# JH_Debug.net
KiCad netlist of a schematic drawn in Altium Designer
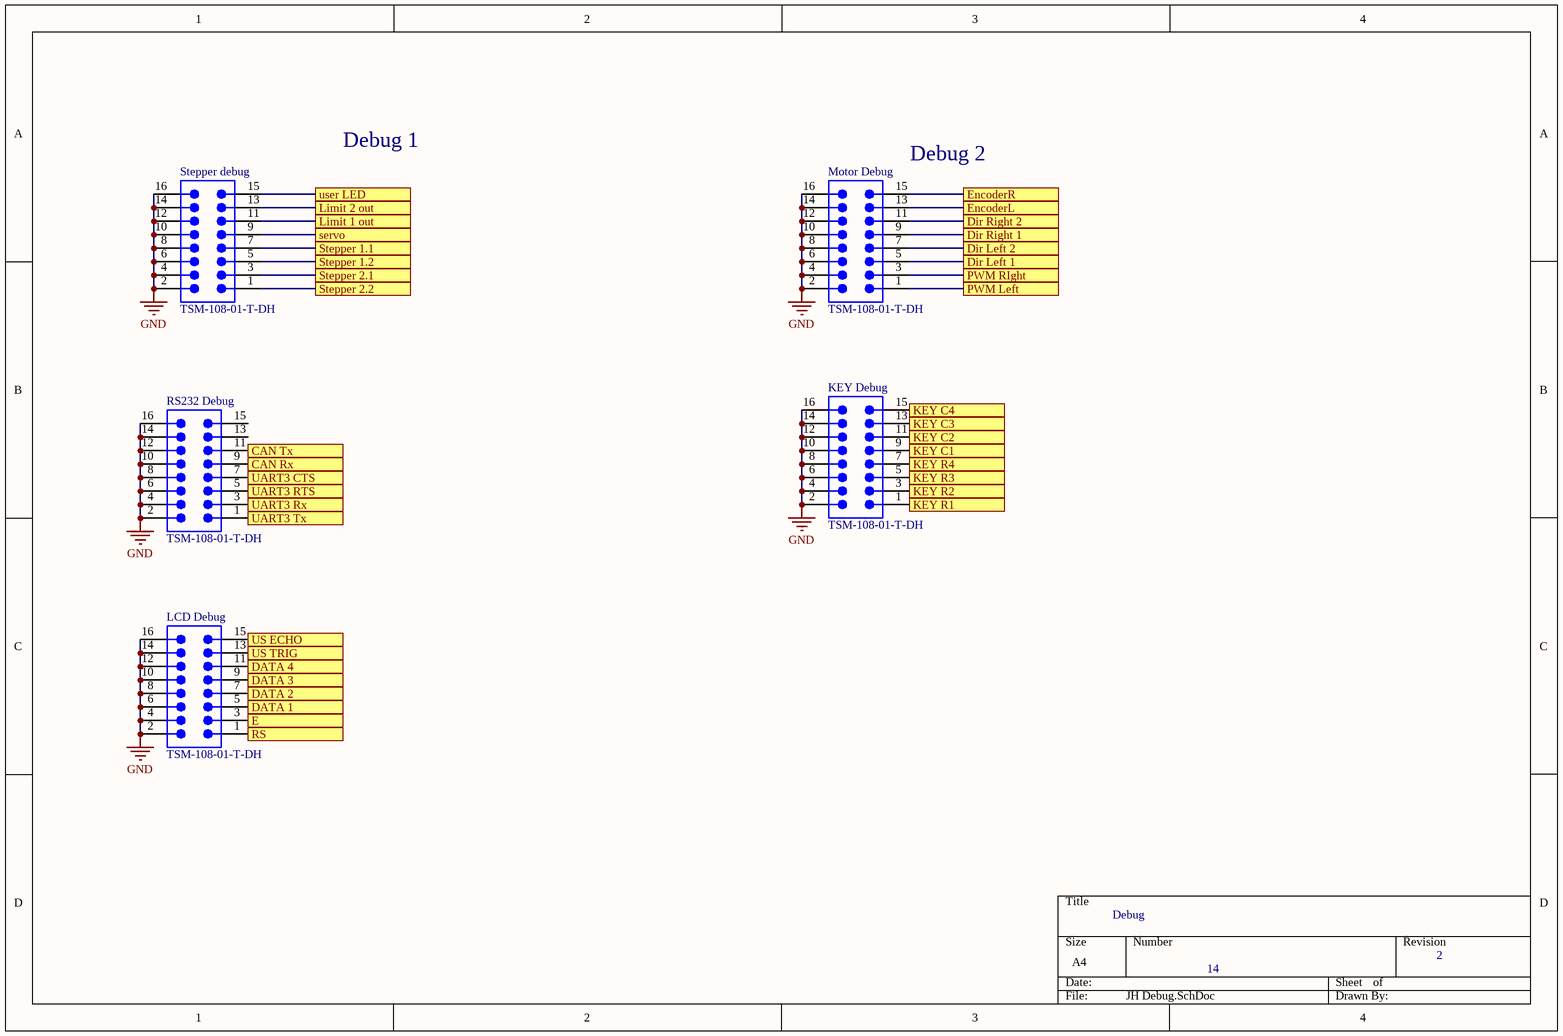
[diagram p0: JH Debug.SchDoc]

(export (version "E")
  (design (tool "Eeschema 10.0.6"))
  (components
    (comp (ref "KEY Debug")
      (value "TSM-108-01-T-DH")
      (footprint "SMTC-TSM-108-01-X-DH")
      (fields (field (name "MANUFACTURER") "Samtec"))
      (libsource (lib "Altium Content Vault") (part "SMTC-TSM-108-01-X-X"))
    )
    (comp (ref "LCD Debug")
      (value "TSM-108-01-T-DH")
      (footprint "SMTC-TSM-108-01-X-DH")
      (fields (field (name "MANUFACTURER") "Samtec"))
      (libsource (lib "Altium Content Vault") (part "SMTC-TSM-108-01-X-X"))
    )
    (comp (ref "Motor Debug")
      (value "TSM-108-01-T-DH")
      (footprint "SMTC-TSM-108-01-X-DH")
      (fields (field (name "MANUFACTURER") "Samtec"))
      (libsource (lib "Altium Content Vault") (part "SMTC-TSM-108-01-X-X"))
    )
    (comp (ref "RS232 Debug")
      (value "TSM-108-01-T-DH")
      (footprint "SMTC-TSM-108-01-X-DH")
      (fields (field (name "MANUFACTURER") "Samtec"))
      (libsource (lib "Altium Content Vault") (part "SMTC-TSM-108-01-X-X"))
    )
    (comp (ref "Stepper debug")
      (value "TSM-108-01-T-DH")
      (footprint "SMTC-TSM-108-01-X-DH")
      (fields (field (name "MANUFACTURER") "Samtec"))
      (libsource (lib "Altium Content Vault") (part "SMTC-TSM-108-01-X-X"))
    )
  )
  (nets
    (net (code "7") (name "/CAN Rx") (class "Default")
      (node (ref "RS232 Debug") (pin "9") (pinfunction "9_9") (pintype "passive"))
    )
    (net (code "8") (name "/CAN Tx") (class "Default")
      (node (ref "RS232 Debug") (pin "11") (pinfunction "11_11") (pintype "passive"))
    )
    (net (code "9") (name "/DATA 1") (class "Default")
      (node (ref "LCD Debug") (pin "5") (pinfunction "5_5") (pintype "passive"))
    )
    (net (code "10") (name "/DATA 2") (class "Default")
      (node (ref "LCD Debug") (pin "7") (pinfunction "7_7") (pintype "passive"))
    )
    (net (code "12") (name "/DATA 3") (class "Default")
      (node (ref "LCD Debug") (pin "9") (pinfunction "9_9") (pintype "passive"))
    )
    (net (code "13") (name "/DATA 4") (class "Default")
      (node (ref "LCD Debug") (pin "11") (pinfunction "11_11") (pintype "passive"))
    )
    (net (code "22") (name "/Dir Left 1") (class "Default")
      (node (ref "Motor Debug") (pin "5") (pinfunction "5_5") (pintype "passive"))
    )
    (net (code "23") (name "/Dir Left 2") (class "Default")
      (node (ref "Motor Debug") (pin "7") (pinfunction "7_7") (pintype "passive"))
    )
    (net (code "24") (name "/Dir Right 1") (class "Default")
      (node (ref "Motor Debug") (pin "9") (pinfunction "9_9") (pintype "passive"))
    )
    (net (code "25") (name "/Dir Right 2") (class "Default")
      (node (ref "Motor Debug") (pin "11") (pinfunction "11_11") (pintype "passive"))
    )
    (net (code "27") (name "/E") (class "Default")
      (node (ref "LCD Debug") (pin "3") (pinfunction "3_3") (pintype "passive"))
    )
    (net (code "28") (name "/EncoderL") (class "Default")
      (node (ref "Motor Debug") (pin "13") (pinfunction "13_13") (pintype "passive"))
    )
    (net (code "29") (name "/EncoderR") (class "Default")
      (node (ref "Motor Debug") (pin "15") (pinfunction "15_15") (pintype "passive"))
    )
    (net (code "30") (name "/KEY C1") (class "Default")
      (node (ref "KEY Debug") (pin "9") (pinfunction "9_9") (pintype "passive"))
    )
    (net (code "37") (name "/KEY C2") (class "Default")
      (node (ref "KEY Debug") (pin "11") (pinfunction "11_11") (pintype "passive"))
    )
    (net (code "38") (name "/KEY C3") (class "Default")
      (node (ref "KEY Debug") (pin "13") (pinfunction "13_13") (pintype "passive"))
    )
    (net (code "39") (name "/KEY C4") (class "Default")
      (node (ref "KEY Debug") (pin "15") (pinfunction "15_15") (pintype "passive"))
    )
    (net (code "40") (name "/KEY R1") (class "Default")
      (node (ref "KEY Debug") (pin "1") (pinfunction "1_1") (pintype "passive"))
    )
    (net (code "41") (name "/KEY R2") (class "Default")
      (node (ref "KEY Debug") (pin "3") (pinfunction "3_3") (pintype "passive"))
    )
    (net (code "42") (name "/KEY R3") (class "Default")
      (node (ref "KEY Debug") (pin "5") (pinfunction "5_5") (pintype "passive"))
    )
    (net (code "43") (name "/KEY R4") (class "Default")
      (node (ref "KEY Debug") (pin "7") (pinfunction "7_7") (pintype "passive"))
    )
    (net (code "44") (name "/Limit 1 out") (class "Default")
      (node (ref "Stepper debug") (pin "11") (pinfunction "11_11") (pintype "passive"))
    )
    (net (code "45") (name "/Limit 2 out") (class "Default")
      (node (ref "Stepper debug") (pin "13") (pinfunction "13_13") (pintype "passive"))
    )
    (net (code "46") (name "/PWM Left") (class "Default")
      (node (ref "Motor Debug") (pin "1") (pinfunction "1_1") (pintype "passive"))
    )
    (net (code "47") (name "/PWM RIght") (class "Default")
      (node (ref "Motor Debug") (pin "3") (pinfunction "3_3") (pintype "passive"))
    )
    (net (code "48") (name "/RS") (class "Default")
      (node (ref "LCD Debug") (pin "1") (pinfunction "1_1") (pintype "passive"))
    )
    (net (code "49") (name "/Stepper 1.1") (class "Default")
      (node (ref "Stepper debug") (pin "7") (pinfunction "7_7") (pintype "passive"))
    )
    (net (code "50") (name "/Stepper 1.2") (class "Default")
      (node (ref "Stepper debug") (pin "5") (pinfunction "5_5") (pintype "passive"))
    )
    (net (code "51") (name "/Stepper 2.1") (class "Default")
      (node (ref "Stepper debug") (pin "3") (pinfunction "3_3") (pintype "passive"))
    )
    (net (code "52") (name "/Stepper 2.2") (class "Default")
      (node (ref "Stepper debug") (pin "1") (pinfunction "1_1") (pintype "passive"))
    )
    (net (code "53") (name "/UART3 CTS") (class "Default")
      (node (ref "RS232 Debug") (pin "7") (pinfunction "7_7") (pintype "passive"))
    )
    (net (code "54") (name "/UART3 RTS") (class "Default")
      (node (ref "RS232 Debug") (pin "5") (pinfunction "5_5") (pintype "passive"))
    )
    (net (code "55") (name "/UART3 Rx") (class "Default")
      (node (ref "RS232 Debug") (pin "3") (pinfunction "3_3") (pintype "passive"))
    )
    (net (code "56") (name "/UART3 Tx") (class "Default")
      (node (ref "RS232 Debug") (pin "1") (pinfunction "1_1") (pintype "passive"))
    )
    (net (code "57") (name "/US ECHO") (class "Default")
      (node (ref "LCD Debug") (pin "15") (pinfunction "15_15") (pintype "passive"))
    )
    (net (code "58") (name "/US TRIG") (class "Default")
      (node (ref "LCD Debug") (pin "13") (pinfunction "13_13") (pintype "passive"))
    )
    (net (code "59") (name "/servo") (class "Default")
      (node (ref "Stepper debug") (pin "9") (pinfunction "9_9") (pintype "passive"))
    )
    (net (code "60") (name "/user LED") (class "Default")
      (node (ref "Stepper debug") (pin "15") (pinfunction "15_15") (pintype "passive"))
    )
    (net (code "61") (name "GND") (class "Default")
      (node (ref "KEY Debug") (pin "10") (pinfunction "10_10") (pintype "passive"))
      (node (ref "KEY Debug") (pin "12") (pinfunction "12_12") (pintype "passive"))
      (node (ref "KEY Debug") (pin "14") (pinfunction "14_14") (pintype "passive"))
      (node (ref "KEY Debug") (pin "16") (pinfunction "16_16") (pintype "passive"))
      (node (ref "KEY Debug") (pin "2") (pinfunction "2_2") (pintype "passive"))
      (node (ref "KEY Debug") (pin "4") (pinfunction "4_4") (pintype "passive"))
      (node (ref "KEY Debug") (pin "6") (pinfunction "6_6") (pintype "passive"))
      (node (ref "KEY Debug") (pin "8") (pinfunction "8_8") (pintype "passive"))
      (node (ref "LCD Debug") (pin "10") (pinfunction "10_10") (pintype "passive"))
      (node (ref "LCD Debug") (pin "12") (pinfunction "12_12") (pintype "passive"))
      (node (ref "LCD Debug") (pin "14") (pinfunction "14_14") (pintype "passive"))
      (node (ref "LCD Debug") (pin "16") (pinfunction "16_16") (pintype "passive"))
      (node (ref "LCD Debug") (pin "2") (pinfunction "2_2") (pintype "passive"))
      (node (ref "LCD Debug") (pin "4") (pinfunction "4_4") (pintype "passive"))
      (node (ref "LCD Debug") (pin "6") (pinfunction "6_6") (pintype "passive"))
      (node (ref "LCD Debug") (pin "8") (pinfunction "8_8") (pintype "passive"))
      (node (ref "Motor Debug") (pin "10") (pinfunction "10_10") (pintype "passive"))
      (node (ref "Motor Debug") (pin "12") (pinfunction "12_12") (pintype "passive"))
      (node (ref "Motor Debug") (pin "14") (pinfunction "14_14") (pintype "passive"))
      (node (ref "Motor Debug") (pin "16") (pinfunction "16_16") (pintype "passive"))
      (node (ref "Motor Debug") (pin "2") (pinfunction "2_2") (pintype "passive"))
      (node (ref "Motor Debug") (pin "4") (pinfunction "4_4") (pintype "passive"))
      (node (ref "Motor Debug") (pin "6") (pinfunction "6_6") (pintype "passive"))
      (node (ref "Motor Debug") (pin "8") (pinfunction "8_8") (pintype "passive"))
      (node (ref "RS232 Debug") (pin "10") (pinfunction "10_10") (pintype "passive"))
      (node (ref "RS232 Debug") (pin "12") (pinfunction "12_12") (pintype "passive"))
      (node (ref "RS232 Debug") (pin "14") (pinfunction "14_14") (pintype "passive"))
      (node (ref "RS232 Debug") (pin "16") (pinfunction "16_16") (pintype "passive"))
      (node (ref "RS232 Debug") (pin "2") (pinfunction "2_2") (pintype "passive"))
      (node (ref "RS232 Debug") (pin "4") (pinfunction "4_4") (pintype "passive"))
      (node (ref "RS232 Debug") (pin "6") (pinfunction "6_6") (pintype "passive"))
      (node (ref "RS232 Debug") (pin "8") (pinfunction "8_8") (pintype "passive"))
      (node (ref "Stepper debug") (pin "10") (pinfunction "10_10") (pintype "passive"))
      (node (ref "Stepper debug") (pin "12") (pinfunction "12_12") (pintype "passive"))
      (node (ref "Stepper debug") (pin "14") (pinfunction "14_14") (pintype "passive"))
      (node (ref "Stepper debug") (pin "16") (pinfunction "16_16") (pintype "passive"))
      (node (ref "Stepper debug") (pin "2") (pinfunction "2_2") (pintype "passive"))
      (node (ref "Stepper debug") (pin "4") (pinfunction "4_4") (pintype "passive"))
      (node (ref "Stepper debug") (pin "6") (pinfunction "6_6") (pintype "passive"))
      (node (ref "Stepper debug") (pin "8") (pinfunction "8_8") (pintype "passive"))
    )
    (net (code "62") (name "unconnected-(RS232 Debug-Pad13)") (class "Default")
      (node (ref "RS232 Debug") (pin "13") (pinfunction "13_13") (pintype "passive"))
    )
    (net (code "63") (name "unconnected-(RS232 Debug-Pad15)") (class "Default")
      (node (ref "RS232 Debug") (pin "15") (pinfunction "15_15") (pintype "passive"))
    )
  )
)
